# Temperature.net
KiCad netlist of a schematic drawn in Altium Designer
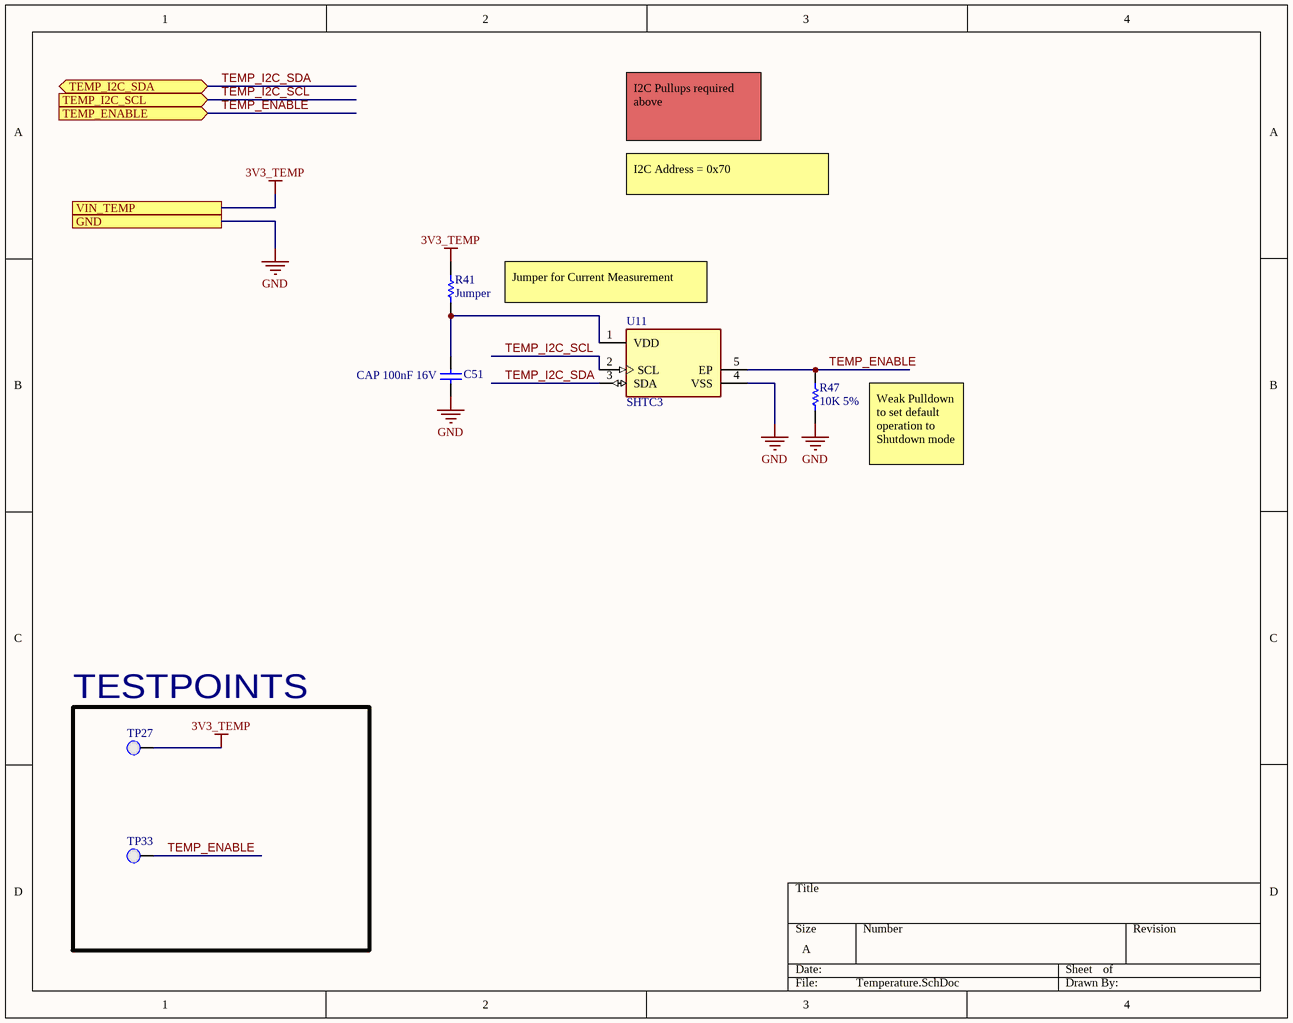
[diagram p0: Temperature.SchDoc]

(export (version "E")
  (design (tool "Eeschema 10.0.6"))
  (components
    (comp (ref "C51")
      (value "CAP 100nF 16V")
      (footprint "CAPC0402(1005)60_M")
      (description "CAP 100nF 16V ±10% 0402 (1005 Metric) Thickness 0.6mm SMD")
      (fields (field (name "TOLERANCE") "Â±10%"))
      (libsource (lib "Altium Content Vault") (part "CAP"))
    )
    (comp (ref "R41")
      (value "Jumper")
      (footprint "RESC0805(2012)_N")
      (description "Jumper 0805 (2012 Metric)")
      (fields (field (name "TOLERANCE") "None"))
      (libsource (lib "Altium Content Vault") (part "RES"))
    )
    (comp (ref "R47")
      (value "10K 5%")
      (footprint "RESC0402(1005)_N")
      (description "10K 0.063W 5% 0402 (1005 Metric)  SMD")
      (fields (field (name "TOLERANCE") "5 %") (field (name "POWER") "0.063 W"))
      (libsource (lib "Altium Content Vault") (part "RES"))
    )
    (comp (ref "TP27")
      (value "0.1\" Pad")
      (footprint "PCBComponent")
      (libsource (lib "Components - 12.02.20 - 18.05") (part "0.1{dblquote} Pad-A.4"))
    )
    (comp (ref "TP33")
      (value "0.1\" Pad")
      (footprint "PCBComponent")
      (libsource (lib "Components - 12.02.20 - 18.05") (part "0.1{dblquote} Pad-A.4"))
    )
    (comp (ref "U11")
      (value "SHTC3")
      (footprint "FP-SHTC3-MFG")
      (description "Humidity Temperature Sensor 0 ~ 100% RH I²C ±2% RH 8s Surface Mount")
      (fields (field (name "MANUFACTURER") "Sensirion"))
      (libsource (lib "Altium Content Vault") (part "92e21da4ceb1e434b50171ab113565b"))
    )
  )
  (nets
    (net (code "1") (name "/TEMP_ENABLE") (class "Default")
      (node (ref "R47") (pin "2") (pinfunction "2_2") (pintype "passive"))
      (node (ref "TP33") (pin "1") (pinfunction "PAD_1") (pintype "passive"))
      (node (ref "U11") (pin "5") (pinfunction "EP_5") (pintype "power_in"))
    )
    (net (code "2") (name "/TEMP_I2C_SCL") (class "Default")
      (node (ref "U11") (pin "2") (pinfunction "SCL_2") (pintype "input"))
    )
    (net (code "3") (name "/TEMP_I2C_SDA") (class "Default")
      (node (ref "U11") (pin "3") (pinfunction "SDA_3") (pintype "bidirectional"))
    )
    (net (code "4") (name "3V3_TEMP") (class "Default")
      (node (ref "R41") (pin "1") (pinfunction "1_1") (pintype "passive"))
      (node (ref "TP27") (pin "1") (pinfunction "PAD_1") (pintype "passive"))
    )
    (net (code "5") (name "GND") (class "Default")
      (node (ref "C51") (pin "1") (pinfunction "1_1") (pintype "passive"))
      (node (ref "R47") (pin "1") (pinfunction "1_1") (pintype "passive"))
      (node (ref "U11") (pin "4") (pinfunction "VSS_4") (pintype "power_in"))
    )
    (net (code "6") (name "Net-(U11-VDD)") (class "Default")
      (node (ref "C51") (pin "2") (pinfunction "2_2") (pintype "passive"))
      (node (ref "R41") (pin "2") (pinfunction "2_2") (pintype "passive"))
      (node (ref "U11") (pin "1") (pinfunction "VDD_1") (pintype "power_in"))
    )
  )
)
